# SCH_nb_v2_2022-07-07.net
KiCad netlist of a schematic drawn in EasyEDA
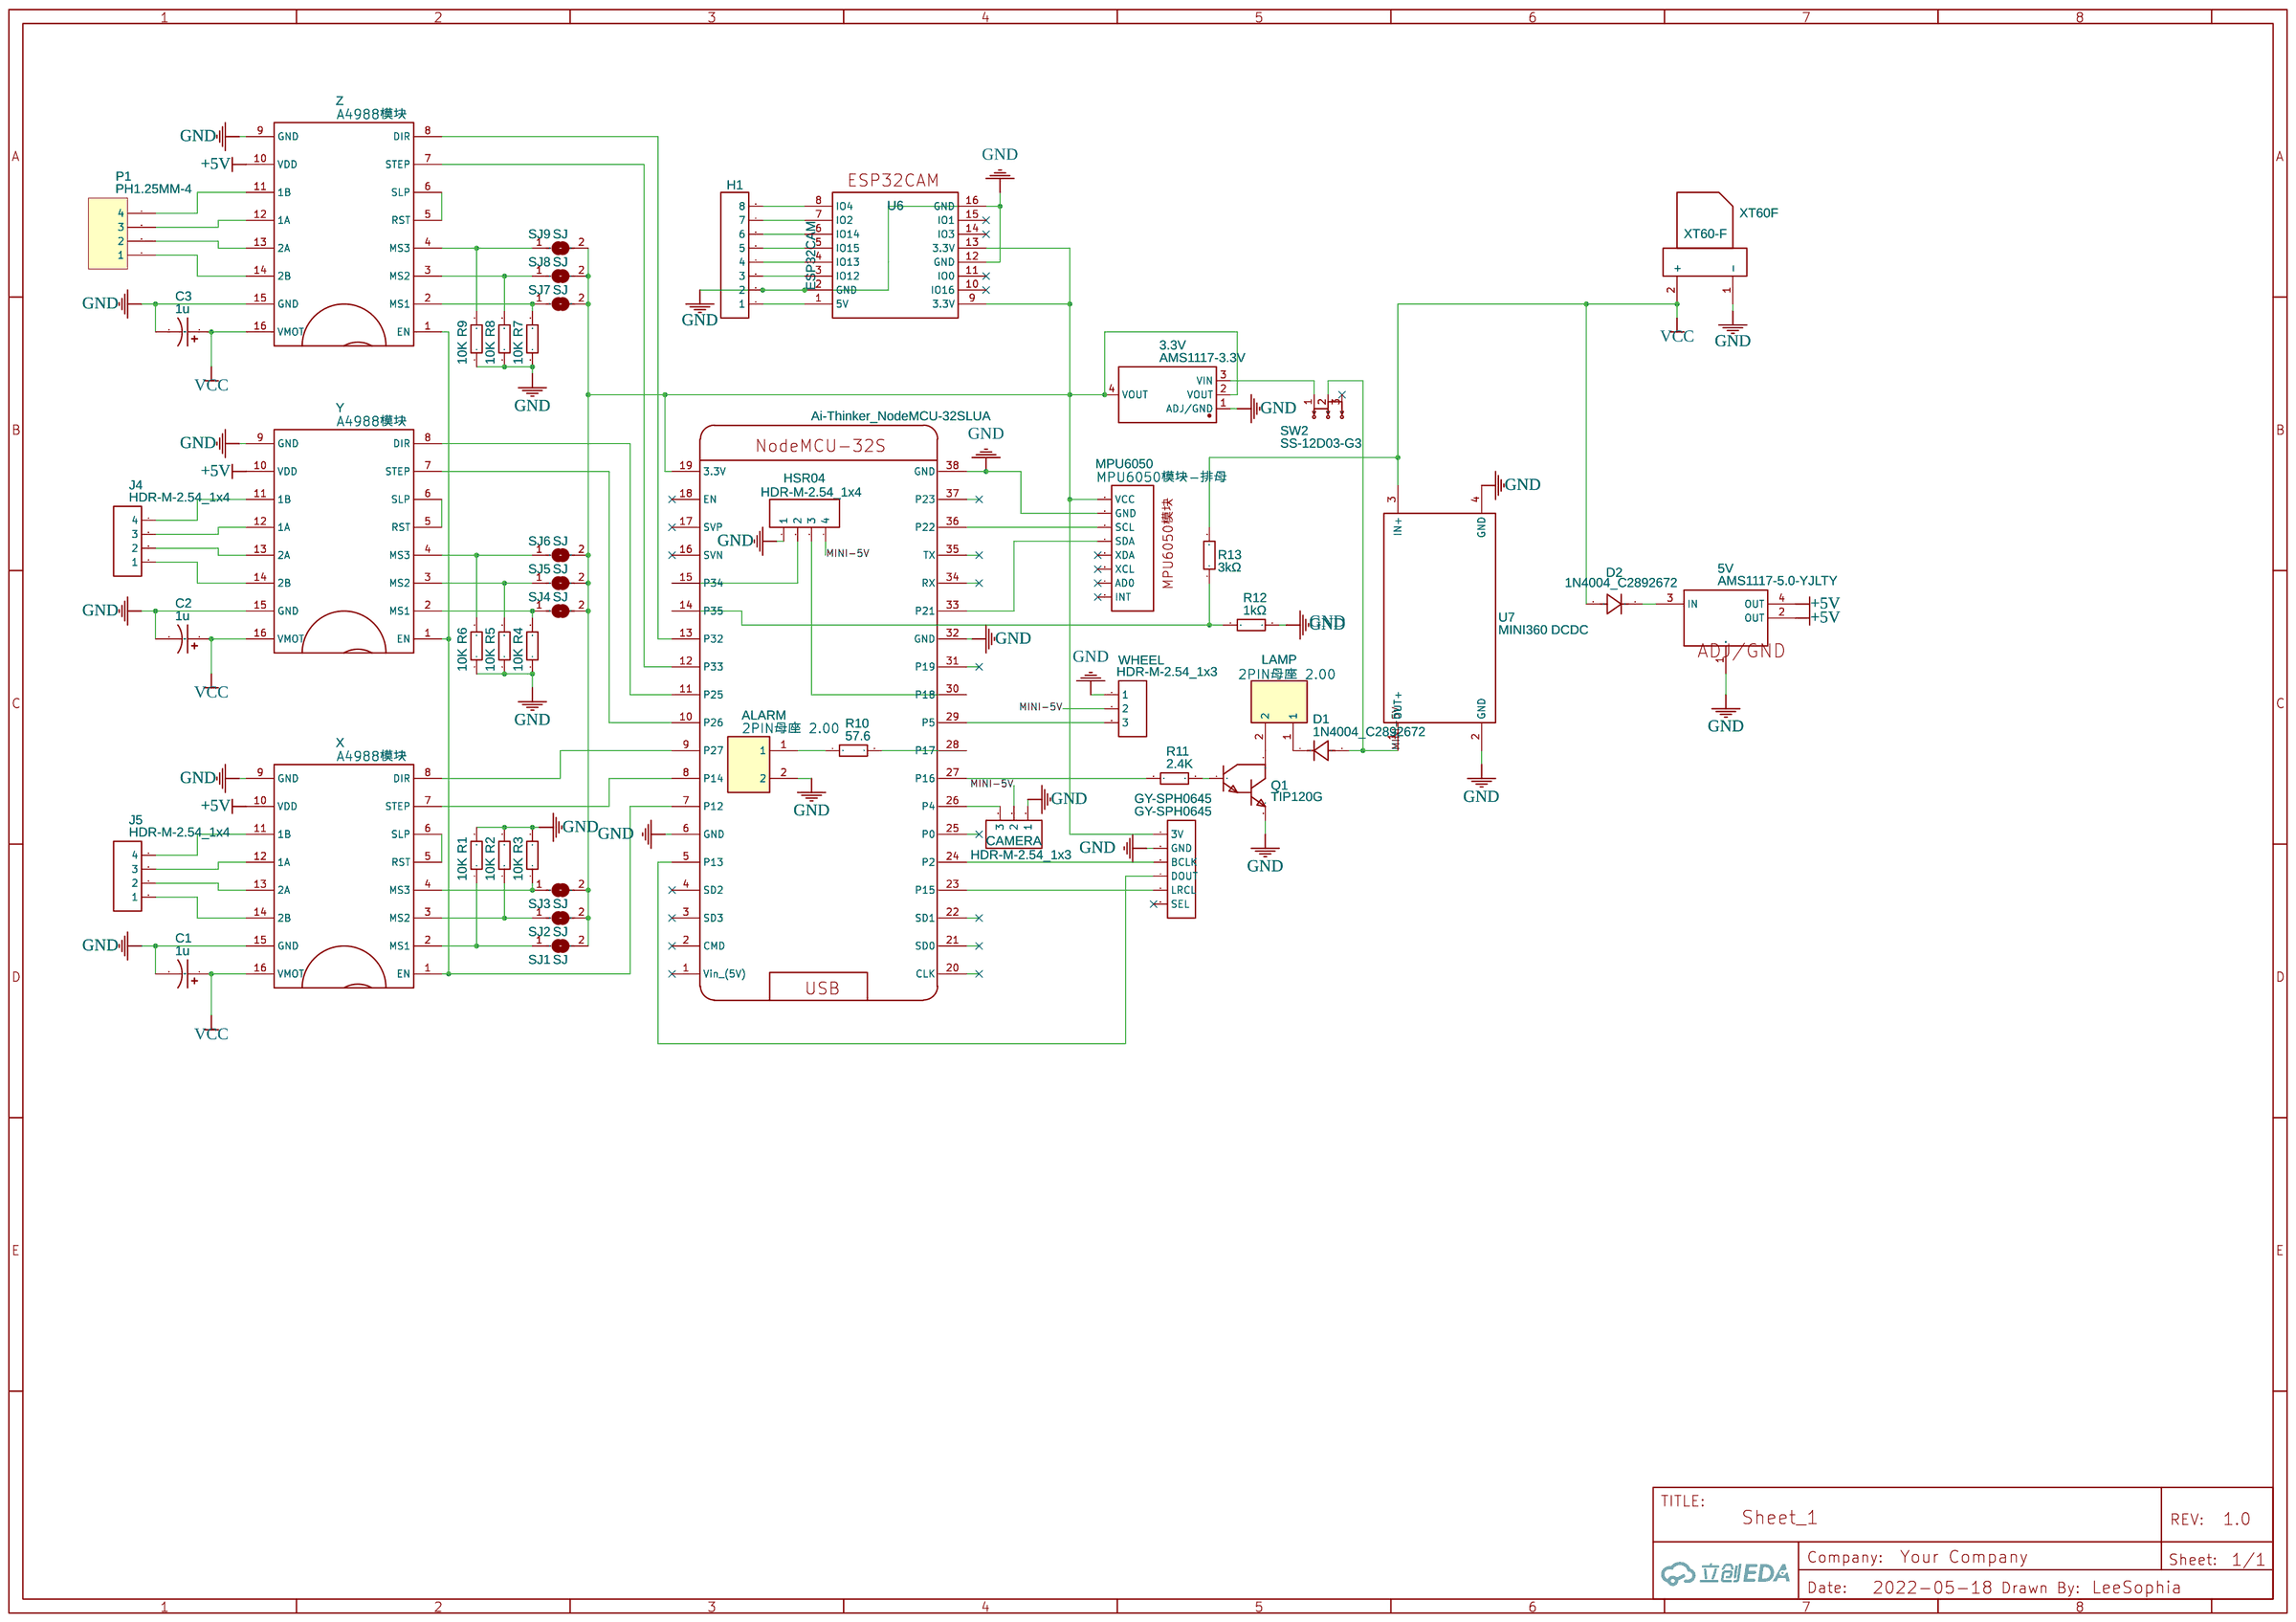
[diagram p0: schematic sheet]

(export (version "E")
  (design (tool "Eeschema 10.0.6"))
  (components
    (comp (ref "3.3V")
      (value "AMS1117-3.3V")
      (fields (field (name "BOM_Supplier Part") "C2688239"))
      (libsource (lib "") (part "AMS1117-3.3V"))
    )
    (comp (ref "5V")
      (value "AMS1117-5.0-YJLTY")
      (fields (field (name "BOM_Supplier Part") "C9900020131"))
      (libsource (lib "") (part "AMS1117-5.0-YJLTY"))
    )
    (comp (ref "ALARM")
      (value "2PIN母座 2.00")
      (fields (field (name "BOM_Manufacturer Part") "PH-2A") (field (name "BOM_Supplier Part") "C2319"))
      (libsource (lib "") (part "2PIN母座 2.00"))
    )
    (comp (ref "C1") (value "1u") (libsource (lib "") (part "CE_TH_D6.3×F2.5_US_1")))
    (comp (ref "C2") (value "1u") (libsource (lib "") (part "CE_TH_D6.3×F2.5_US")))
    (comp (ref "C3") (value "1u") (libsource (lib "") (part "CE_TH_D6.3×F2.5_US")))
    (comp (ref "CAMERA")
      (value "HDR-M-2.54_1x3")
      (fields (field (name "BOM_Supplier Part") "C180248"))
      (libsource (lib "") (part "HDR-M-2.54_1x3_1"))
    )
    (comp (ref "D1")
      (value "1N4004_C2892672")
      (fields (field (name "BOM_Manufacturer Part") "1N4004") (field (name "BOM_Supplier Part") "C2892672"))
      (libsource (lib "") (part "1N4004_C2892672_1"))
    )
    (comp (ref "D2")
      (value "1N4004_C2892672")
      (fields (field (name "BOM_Manufacturer Part") "1N4004") (field (name "BOM_Supplier Part") "C2892672"))
      (libsource (lib "") (part "1N4004_C2892672"))
    )
    (comp (ref "GY-SPH0645")
      (value "GY-SPH0645")
      (fields (field (name "BOM_Supplier Part") "C40877"))
      (libsource (lib "") (part "HDR-F-2.54_1x6"))
    )
    (comp (ref "H1")
      (value "H1")
      (fields (field (name "BOM_Supplier Part") "C225505"))
      (libsource (lib "") (part "HDR-F-2.54_1x8"))
    )
    (comp (ref "HSR04")
      (value "HDR-M-2.54_1x4")
      (fields (field (name "BOM_Supplier Part") "C124378"))
      (libsource (lib "") (part "HDR-M-2.54_1x4_1"))
    )
    (comp (ref "J4")
      (value "HDR-M-2.54_1x4")
      (fields (field (name "BOM_Supplier Part") "C124378"))
      (libsource (lib "") (part "HDR-M-2.54_1x4"))
    )
    (comp (ref "J5")
      (value "HDR-M-2.54_1x4")
      (fields (field (name "BOM_Supplier Part") "C124378"))
      (libsource (lib "") (part "HDR-M-2.54_1x4"))
    )
    (comp (ref "LAMP")
      (value "2PIN母座 2.00")
      (fields (field (name "BOM_Manufacturer Part") "PH-2A") (field (name "BOM_Supplier Part") "C2319"))
      (libsource (lib "") (part "2PIN母座 2.00_1"))
    )
    (comp (ref "MPU6050") (value "MPU6050模块-排母") (libsource (lib "") (part "MPU6050模块-排母")))
    (comp (ref "P1") (value "PH1.25MM-4") (libsource (lib "") (part "PH1.25MM-4")))
    (comp (ref "Q1")
      (value "TIP120G")
      (fields (field (name "BOM_Supplier Part") "C223613"))
      (libsource (lib "") (part "TIP120G"))
    )
    (comp (ref "R1")
      (value "10K")
      (fields
        (field (name "BOM_Manufacturer Part") "RMCF0603JT10K0")
        (field (name "BOM_Supplier Part") "C238881")
      )
      (libsource (lib "") (part "RMCF0603JT10K0"))
    )
    (comp (ref "R2")
      (value "10K")
      (fields
        (field (name "BOM_Manufacturer Part") "RMCF0603JT10K0")
        (field (name "BOM_Supplier Part") "C238881")
      )
      (libsource (lib "") (part "RMCF0603JT10K0"))
    )
    (comp (ref "R3")
      (value "10K")
      (fields
        (field (name "BOM_Manufacturer Part") "RMCF0603JT10K0")
        (field (name "BOM_Supplier Part") "C238881")
      )
      (libsource (lib "") (part "RMCF0603JT10K0"))
    )
    (comp (ref "R4")
      (value "10K")
      (fields
        (field (name "BOM_Manufacturer Part") "RMCF0603JT10K0")
        (field (name "BOM_Supplier Part") "C238881")
      )
      (libsource (lib "") (part "RMCF0603JT10K0"))
    )
    (comp (ref "R5")
      (value "10K")
      (fields
        (field (name "BOM_Manufacturer Part") "RMCF0603JT10K0")
        (field (name "BOM_Supplier Part") "C238881")
      )
      (libsource (lib "") (part "RMCF0603JT10K0"))
    )
    (comp (ref "R6")
      (value "10K")
      (fields
        (field (name "BOM_Manufacturer Part") "RMCF0603JT10K0")
        (field (name "BOM_Supplier Part") "C238881")
      )
      (libsource (lib "") (part "RMCF0603JT10K0"))
    )
    (comp (ref "R7")
      (value "10K")
      (fields
        (field (name "BOM_Manufacturer Part") "RMCF0603JT10K0")
        (field (name "BOM_Supplier Part") "C238881")
      )
      (libsource (lib "") (part "RMCF0603JT10K0"))
    )
    (comp (ref "R8")
      (value "10K")
      (fields
        (field (name "BOM_Manufacturer Part") "RMCF0603JT10K0")
        (field (name "BOM_Supplier Part") "C238881")
      )
      (libsource (lib "") (part "RMCF0603JT10K0"))
    )
    (comp (ref "R9")
      (value "10K")
      (fields
        (field (name "BOM_Manufacturer Part") "RMCF0603JT10K0")
        (field (name "BOM_Supplier Part") "C238881")
      )
      (libsource (lib "") (part "RMCF0603JT10K0"))
    )
    (comp (ref "R10")
      (value "57.6")
      (fields
        (field (name "BOM_Manufacturer Part") "RC0603FR-0757R6L")
        (field (name "BOM_Supplier Part") "C245984")
      )
      (libsource (lib "") (part "RC0603FR-0757R6L"))
    )
    (comp (ref "R11")
      (value "2.4K")
      (fields
        (field (name "BOM_Manufacturer Part") "AC0603FR-072K4L")
        (field (name "BOM_Supplier Part") "C144674")
      )
      (libsource (lib "") (part "AC0603FR-072K4L"))
    )
    (comp (ref "R12")
      (value "1kΩ")
      (fields
        (field (name "BOM_Manufacturer Part") "0603WAF1101T5E")
        (field (name "BOM_Supplier Part") "C22764")
      )
      (libsource (lib "") (part "0603WAF1101T5E"))
    )
    (comp (ref "R13")
      (value "3kΩ")
      (fields
        (field (name "BOM_Manufacturer Part") "RM06FTN3001")
        (field (name "BOM_Supplier Part") "C147818")
      )
      (libsource (lib "") (part "RM06FTN3001"))
    )
    (comp (ref "SJ1") (value "SJ") (libsource (lib "") (part "SJ")))
    (comp (ref "SJ2") (value "SJ") (libsource (lib "") (part "SJ")))
    (comp (ref "SJ3") (value "SJ") (libsource (lib "") (part "SJ")))
    (comp (ref "SJ4") (value "SJ") (libsource (lib "") (part "SJ")))
    (comp (ref "SJ5") (value "SJ") (libsource (lib "") (part "SJ")))
    (comp (ref "SJ6") (value "SJ") (libsource (lib "") (part "SJ")))
    (comp (ref "SJ7") (value "SJ") (libsource (lib "") (part "SJ")))
    (comp (ref "SJ8") (value "SJ") (libsource (lib "") (part "SJ")))
    (comp (ref "SJ9") (value "SJ") (libsource (lib "") (part "SJ")))
    (comp (ref "SW2")
      (value "SS-12D03-G3")
      (fields (field (name "BOM_Supplier Part") "C698224"))
      (libsource (lib "") (part "SS-12D03-G3"))
    )
    (comp (ref "U2")
      (value "Ai-Thinker_NodeMCU-32SLUA")
      (fields
        (field (name "BOM_Manufacturer Part") "NodeMCU-32SLua")
        (field (name "BOM_Supplier Part") "C111436")
      )
      (libsource (lib "") (part "Ai-Thinker_NodeMCU-32SLUA"))
    )
    (comp (ref "U6") (value "ESP32CAM") (libsource (lib "") (part "ESP32CAM")))
    (comp (ref "U7") (value "MINI360 DCDC") (libsource (lib "") (part "MINI360 DCDC")))
    (comp (ref "WHEEL")
      (value "HDR-M-2.54_1x3")
      (fields (field (name "BOM_Supplier Part") "C180248"))
      (libsource (lib "") (part "HDR-M-2.54_1x3"))
    )
    (comp (ref "X") (value "A4988模块") (libsource (lib "") (part "A4988模块_1")))
    (comp (ref "XT60F") (value "XT60-F") (libsource (lib "") (part "XT60-F")))
    (comp (ref "Y") (value "A4988模块") (libsource (lib "") (part "A4988模块_2")))
    (comp (ref "Z") (value "A4988模块") (libsource (lib "") (part "A4988模块")))
  )
  (nets
    (net (code "1") (name "+5V") (class "Default")
      (node (ref "5V") (pin "2") (pinfunction "OUT_2") (pintype "passive"))
      (node (ref "5V") (pin "4") (pinfunction "OUT_4") (pintype "passive"))
      (node (ref "X") (pin "10") (pinfunction "VDD_10") (pintype "passive"))
      (node (ref "Y") (pin "10") (pinfunction "VDD_10") (pintype "passive"))
      (node (ref "Z") (pin "10") (pinfunction "VDD_10") (pintype "passive"))
    )
    (net (code "2") (name "/MINI-5V") (class "Default")
      (node (ref "CAMERA") (pin "2") (pinfunction "2_2") (pintype "input"))
      (node (ref "D1") (pin "2") (pinfunction "A_2") (pintype "unspecified"))
      (node (ref "HSR04") (pin "4") (pinfunction "4_4") (pintype "unspecified"))
      (node (ref "SW2") (pin "2") (pinfunction "2_2") (pintype "unspecified"))
      (node (ref "U7") (pin "1") (pinfunction "OUT+_1") (pintype "unspecified"))
      (node (ref "WHEEL") (pin "2") (pinfunction "2_2") (pintype "input"))
    )
    (net (code "3") (name "GND") (class "Default")
      (node (ref "3.3V") (pin "1") (pinfunction "ADJ/GND_1") (pintype "unspecified"))
      (node (ref "5V") (pin "1") (pinfunction "ADJ/GND_1") (pintype "passive"))
      (node (ref "ALARM") (pin "2") (pinfunction "2_2") (pintype "input"))
      (node (ref "C1") (pin "2") (pinfunction "2_2") (pintype "unspecified"))
      (node (ref "C2") (pin "2") (pinfunction "2_2") (pintype "unspecified"))
      (node (ref "C3") (pin "2") (pinfunction "2_2") (pintype "unspecified"))
      (node (ref "CAMERA") (pin "1") (pinfunction "1_1") (pintype "input"))
      (node (ref "GY-SPH0645") (pin "2") (pinfunction "GND_2") (pintype "input"))
      (node (ref "H1") (pin "2") (pinfunction "2_2") (pintype "unspecified"))
      (node (ref "HSR04") (pin "1") (pinfunction "1_1") (pintype "unspecified"))
      (node (ref "MPU6050") (pin "2") (pinfunction "GND_2") (pintype "input"))
      (node (ref "Q1") (pin "3") (pinfunction "E_3") (pintype "unspecified"))
      (node (ref "R1") (pin "2") (pinfunction "2_2") (pintype "unspecified"))
      (node (ref "R12") (pin "2") (pinfunction "2_2") (pintype "input"))
      (node (ref "R2") (pin "2") (pinfunction "2_2") (pintype "unspecified"))
      (node (ref "R3") (pin "2") (pinfunction "2_2") (pintype "unspecified"))
      (node (ref "R4") (pin "1") (pinfunction "1_1") (pintype "unspecified"))
      (node (ref "R5") (pin "1") (pinfunction "1_1") (pintype "unspecified"))
      (node (ref "R6") (pin "1") (pinfunction "1_1") (pintype "unspecified"))
      (node (ref "R7") (pin "1") (pinfunction "1_1") (pintype "unspecified"))
      (node (ref "R8") (pin "1") (pinfunction "1_1") (pintype "unspecified"))
      (node (ref "R9") (pin "1") (pinfunction "1_1") (pintype "unspecified"))
      (node (ref "U2") (pin "32") (pinfunction "GND_32") (pintype "unspecified"))
      (node (ref "U2") (pin "38") (pinfunction "GND_38") (pintype "unspecified"))
      (node (ref "U2") (pin "6") (pinfunction "GND_6") (pintype "unspecified"))
      (node (ref "U6") (pin "12") (pinfunction "GND_12") (pintype "unspecified"))
      (node (ref "U6") (pin "16") (pinfunction "GND_16") (pintype "unspecified"))
      (node (ref "U6") (pin "2") (pinfunction "GND_2") (pintype "unspecified"))
      (node (ref "U7") (pin "2") (pinfunction "GND_2") (pintype "unspecified"))
      (node (ref "U7") (pin "4") (pinfunction "GND_4") (pintype "unspecified"))
      (node (ref "WHEEL") (pin "1") (pinfunction "1_1") (pintype "input"))
      (node (ref "X") (pin "15") (pinfunction "GND_15") (pintype "passive"))
      (node (ref "X") (pin "9") (pinfunction "GND_9") (pintype "passive"))
      (node (ref "XT60F") (pin "1") (pinfunction "-_1") (pintype "unspecified"))
      (node (ref "Y") (pin "15") (pinfunction "GND_15") (pintype "passive"))
      (node (ref "Y") (pin "9") (pinfunction "GND_9") (pintype "passive"))
      (node (ref "Z") (pin "15") (pinfunction "GND_15") (pintype "passive"))
      (node (ref "Z") (pin "9") (pinfunction "GND_9") (pintype "passive"))
    )
    (net (code "4") (name "Net-(3.3V-VIN)") (class "Default")
      (node (ref "3.3V") (pin "3") (pinfunction "VIN_3") (pintype "unspecified"))
      (node (ref "SW2") (pin "1") (pinfunction "1_1") (pintype "unspecified"))
    )
    (net (code "5") (name "Net-(5V-IN)") (class "Default")
      (node (ref "5V") (pin "3") (pinfunction "IN_3") (pintype "passive"))
      (node (ref "D2") (pin "1") (pinfunction "K_1") (pintype "unspecified"))
    )
    (net (code "6") (name "Net-(ALARM-Pad1)") (class "Default")
      (node (ref "ALARM") (pin "1") (pinfunction "1_1") (pintype "input"))
      (node (ref "R10") (pin "1") (pinfunction "1_1") (pintype "unspecified"))
    )
    (net (code "7") (name "Net-(D1-K)") (class "Default")
      (node (ref "D1") (pin "1") (pinfunction "K_1") (pintype "unspecified"))
      (node (ref "LAMP") (pin "1") (pinfunction "1_1") (pintype "input"))
    )
    (net (code "8") (name "Net-(GY-SPH0645-3V)") (class "Default")
      (node (ref "3.3V") (pin "2") (pinfunction "VOUT_2") (pintype "unspecified"))
      (node (ref "3.3V") (pin "4") (pinfunction "VOUT_4") (pintype "unspecified"))
      (node (ref "GY-SPH0645") (pin "1") (pinfunction "3V_1") (pintype "input"))
      (node (ref "MPU6050") (pin "1") (pinfunction "VCC_1") (pintype "input"))
      (node (ref "SJ1") (pin "2") (pinfunction "2_2") (pintype "bidirectional"))
      (node (ref "SJ2") (pin "2") (pinfunction "2_2") (pintype "bidirectional"))
      (node (ref "SJ3") (pin "2") (pinfunction "2_2") (pintype "bidirectional"))
      (node (ref "SJ4") (pin "2") (pinfunction "2_2") (pintype "bidirectional"))
      (node (ref "SJ5") (pin "2") (pinfunction "2_2") (pintype "bidirectional"))
      (node (ref "SJ6") (pin "2") (pinfunction "2_2") (pintype "bidirectional"))
      (node (ref "SJ7") (pin "2") (pinfunction "2_2") (pintype "bidirectional"))
      (node (ref "SJ8") (pin "2") (pinfunction "2_2") (pintype "bidirectional"))
      (node (ref "SJ9") (pin "2") (pinfunction "2_2") (pintype "bidirectional"))
      (node (ref "U2") (pin "19") (pinfunction "3.3V_19") (pintype "unspecified"))
      (node (ref "U6") (pin "13") (pinfunction "3.3V_13") (pintype "unspecified"))
      (node (ref "U6") (pin "9") (pinfunction "3.3V_9") (pintype "unspecified"))
    )
    (net (code "9") (name "Net-(GY-SPH0645-BCLK)") (class "Default")
      (node (ref "GY-SPH0645") (pin "3") (pinfunction "BCLK_3") (pintype "input"))
      (node (ref "U2") (pin "24") (pinfunction "P2_24") (pintype "unspecified"))
    )
    (net (code "10") (name "Net-(GY-SPH0645-DOUT)") (class "Default")
      (node (ref "GY-SPH0645") (pin "4") (pinfunction "DOUT_4") (pintype "input"))
      (node (ref "U2") (pin "5") (pinfunction "P13_5") (pintype "unspecified"))
    )
    (net (code "11") (name "Net-(GY-SPH0645-LRCL)") (class "Default")
      (node (ref "GY-SPH0645") (pin "5") (pinfunction "LRCL_5") (pintype "input"))
      (node (ref "U2") (pin "23") (pinfunction "P15_23") (pintype "unspecified"))
    )
    (net (code "12") (name "Net-(MPU6050-SCL)") (class "Default")
      (node (ref "MPU6050") (pin "3") (pinfunction "SCL_3") (pintype "input"))
      (node (ref "U2") (pin "36") (pinfunction "P22_36") (pintype "unspecified"))
    )
    (net (code "13") (name "Net-(MPU6050-SDA)") (class "Default")
      (node (ref "MPU6050") (pin "4") (pinfunction "SDA_4") (pintype "input"))
      (node (ref "U2") (pin "33") (pinfunction "P21_33") (pintype "unspecified"))
    )
    (net (code "14") (name "Net-(Q1-B)") (class "Default")
      (node (ref "Q1") (pin "1") (pinfunction "B_1") (pintype "unspecified"))
      (node (ref "R11") (pin "2") (pinfunction "2_2") (pintype "unspecified"))
    )
    (net (code "15") (name "Net-(Q1-C)") (class "Default")
      (node (ref "LAMP") (pin "2") (pinfunction "2_2") (pintype "input"))
      (node (ref "Q1") (pin "2") (pinfunction "C_2") (pintype "unspecified"))
    )
    (net (code "16") (name "Net-(U2-P4)") (class "Default")
      (node (ref "CAMERA") (pin "3") (pinfunction "3_3") (pintype "input"))
      (node (ref "U2") (pin "26") (pinfunction "P4_26") (pintype "unspecified"))
    )
    (net (code "17") (name "Net-(U2-P5)") (class "Default")
      (node (ref "U2") (pin "29") (pinfunction "P5_29") (pintype "unspecified"))
      (node (ref "WHEEL") (pin "3") (pinfunction "3_3") (pintype "input"))
    )
    (net (code "18") (name "Net-(U2-P12)") (class "Default")
      (node (ref "U2") (pin "7") (pinfunction "P12_7") (pintype "unspecified"))
      (node (ref "X") (pin "1") (pinfunction "EN_1") (pintype "input"))
      (node (ref "Y") (pin "1") (pinfunction "EN_1") (pintype "input"))
      (node (ref "Z") (pin "1") (pinfunction "EN_1") (pintype "input"))
    )
    (net (code "19") (name "Net-(U2-P14)") (class "Default")
      (node (ref "U2") (pin "8") (pinfunction "P14_8") (pintype "unspecified"))
      (node (ref "X") (pin "7") (pinfunction "STEP_7") (pintype "input"))
    )
    (net (code "20") (name "Net-(U2-P16)") (class "Default")
      (node (ref "R11") (pin "1") (pinfunction "1_1") (pintype "unspecified"))
      (node (ref "U2") (pin "27") (pinfunction "P16_27") (pintype "unspecified"))
    )
    (net (code "21") (name "Net-(U2-P17)") (class "Default")
      (node (ref "R10") (pin "2") (pinfunction "2_2") (pintype "unspecified"))
      (node (ref "U2") (pin "28") (pinfunction "P17_28") (pintype "unspecified"))
    )
    (net (code "22") (name "Net-(U2-P18)") (class "Default")
      (node (ref "HSR04") (pin "3") (pinfunction "3_3") (pintype "unspecified"))
      (node (ref "U2") (pin "30") (pinfunction "P18_30") (pintype "unspecified"))
    )
    (net (code "23") (name "Net-(U2-P25)") (class "Default")
      (node (ref "U2") (pin "11") (pinfunction "P25_11") (pintype "unspecified"))
      (node (ref "Y") (pin "8") (pinfunction "DIR_8") (pintype "input"))
    )
    (net (code "24") (name "Net-(U2-P26)") (class "Default")
      (node (ref "U2") (pin "10") (pinfunction "P26_10") (pintype "unspecified"))
      (node (ref "Y") (pin "7") (pinfunction "STEP_7") (pintype "input"))
    )
    (net (code "25") (name "Net-(U2-P27)") (class "Default")
      (node (ref "U2") (pin "9") (pinfunction "P27_9") (pintype "unspecified"))
      (node (ref "X") (pin "8") (pinfunction "DIR_8") (pintype "input"))
    )
    (net (code "26") (name "Net-(U2-P32)") (class "Default")
      (node (ref "U2") (pin "13") (pinfunction "P32_13") (pintype "unspecified"))
      (node (ref "Z") (pin "8") (pinfunction "DIR_8") (pintype "input"))
    )
    (net (code "27") (name "Net-(U2-P33)") (class "Default")
      (node (ref "U2") (pin "12") (pinfunction "P33_12") (pintype "unspecified"))
      (node (ref "Z") (pin "7") (pinfunction "STEP_7") (pintype "input"))
    )
    (net (code "28") (name "Net-(U2-P34)") (class "Default")
      (node (ref "HSR04") (pin "2") (pinfunction "2_2") (pintype "unspecified"))
      (node (ref "U2") (pin "15") (pinfunction "P34_15") (pintype "unspecified"))
    )
    (net (code "29") (name "Net-(U2-P35)") (class "Default")
      (node (ref "R12") (pin "1") (pinfunction "1_1") (pintype "input"))
      (node (ref "R13") (pin "1") (pinfunction "1_1") (pintype "unspecified"))
      (node (ref "U2") (pin "14") (pinfunction "P35_14") (pintype "unspecified"))
    )
    (net (code "30") (name "Net-(U6-5V)") (class "Default")
      (node (ref "H1") (pin "1") (pinfunction "1_1") (pintype "unspecified"))
      (node (ref "U6") (pin "1") (pinfunction "5V_1") (pintype "unspecified"))
    )
    (net (code "31") (name "Net-(U6-IO2)") (class "Default")
      (node (ref "H1") (pin "7") (pinfunction "7_7") (pintype "unspecified"))
      (node (ref "U6") (pin "7") (pinfunction "IO2_7") (pintype "unspecified"))
    )
    (net (code "32") (name "Net-(U6-IO4)") (class "Default")
      (node (ref "H1") (pin "8") (pinfunction "8_8") (pintype "unspecified"))
      (node (ref "U6") (pin "8") (pinfunction "IO4_8") (pintype "unspecified"))
    )
    (net (code "33") (name "Net-(U6-IO12)") (class "Default")
      (node (ref "H1") (pin "3") (pinfunction "3_3") (pintype "unspecified"))
      (node (ref "U6") (pin "3") (pinfunction "IO12_3") (pintype "unspecified"))
    )
    (net (code "34") (name "Net-(U6-IO13)") (class "Default")
      (node (ref "H1") (pin "4") (pinfunction "4_4") (pintype "unspecified"))
      (node (ref "U6") (pin "4") (pinfunction "IO13_4") (pintype "unspecified"))
    )
    (net (code "35") (name "Net-(U6-IO14)") (class "Default")
      (node (ref "H1") (pin "6") (pinfunction "6_6") (pintype "unspecified"))
      (node (ref "U6") (pin "6") (pinfunction "IO14_6") (pintype "unspecified"))
    )
    (net (code "36") (name "Net-(U6-IO15)") (class "Default")
      (node (ref "H1") (pin "5") (pinfunction "5_5") (pintype "unspecified"))
      (node (ref "U6") (pin "5") (pinfunction "IO15_5") (pintype "unspecified"))
    )
    (net (code "37") (name "Net-(X-1A)") (class "Default")
      (node (ref "J5") (pin "3") (pinfunction "3_3") (pintype "unspecified"))
      (node (ref "X") (pin "12") (pinfunction "1A_12") (pintype "output"))
    )
    (net (code "38") (name "Net-(X-1B)") (class "Default")
      (node (ref "J5") (pin "4") (pinfunction "4_4") (pintype "unspecified"))
      (node (ref "X") (pin "11") (pinfunction "1B_11") (pintype "output"))
    )
    (net (code "39") (name "Net-(X-2A)") (class "Default")
      (node (ref "J5") (pin "2") (pinfunction "2_2") (pintype "unspecified"))
      (node (ref "X") (pin "13") (pinfunction "2A_13") (pintype "output"))
    )
    (net (code "40") (name "Net-(X-2B)") (class "Default")
      (node (ref "J5") (pin "1") (pinfunction "1_1") (pintype "unspecified"))
      (node (ref "X") (pin "14") (pinfunction "2B_14") (pintype "output"))
    )
    (net (code "41") (name "Net-(X-MS1)") (class "Default")
      (node (ref "R1") (pin "1") (pinfunction "1_1") (pintype "unspecified"))
      (node (ref "SJ1") (pin "1") (pinfunction "1_1") (pintype "bidirectional"))
      (node (ref "X") (pin "2") (pinfunction "MS1_2") (pintype "input"))
    )
    (net (code "42") (name "Net-(X-MS2)") (class "Default")
      (node (ref "R2") (pin "1") (pinfunction "1_1") (pintype "unspecified"))
      (node (ref "SJ2") (pin "1") (pinfunction "1_1") (pintype "bidirectional"))
      (node (ref "X") (pin "3") (pinfunction "MS2_3") (pintype "input"))
    )
    (net (code "43") (name "Net-(X-MS3)") (class "Default")
      (node (ref "R3") (pin "1") (pinfunction "1_1") (pintype "unspecified"))
      (node (ref "SJ3") (pin "1") (pinfunction "1_1") (pintype "bidirectional"))
      (node (ref "X") (pin "4") (pinfunction "MS3_4") (pintype "input"))
    )
    (net (code "44") (name "Net-(X-RST)") (class "Default")
      (node (ref "X") (pin "5") (pinfunction "RST_5") (pintype "input"))
      (node (ref "X") (pin "6") (pinfunction "SLP_6") (pintype "input"))
    )
    (net (code "45") (name "Net-(Y-1A)") (class "Default")
      (node (ref "J4") (pin "3") (pinfunction "3_3") (pintype "unspecified"))
      (node (ref "Y") (pin "12") (pinfunction "1A_12") (pintype "output"))
    )
    (net (code "46") (name "Net-(Y-1B)") (class "Default")
      (node (ref "J4") (pin "4") (pinfunction "4_4") (pintype "unspecified"))
      (node (ref "Y") (pin "11") (pinfunction "1B_11") (pintype "output"))
    )
    (net (code "47") (name "Net-(Y-2A)") (class "Default")
      (node (ref "J4") (pin "2") (pinfunction "2_2") (pintype "unspecified"))
      (node (ref "Y") (pin "13") (pinfunction "2A_13") (pintype "output"))
    )
    (net (code "48") (name "Net-(Y-2B)") (class "Default")
      (node (ref "J4") (pin "1") (pinfunction "1_1") (pintype "unspecified"))
      (node (ref "Y") (pin "14") (pinfunction "2B_14") (pintype "output"))
    )
    (net (code "49") (name "Net-(Y-MS1)") (class "Default")
      (node (ref "R4") (pin "2") (pinfunction "2_2") (pintype "unspecified"))
      (node (ref "SJ4") (pin "1") (pinfunction "1_1") (pintype "bidirectional"))
      (node (ref "Y") (pin "2") (pinfunction "MS1_2") (pintype "input"))
    )
    (net (code "50") (name "Net-(Y-MS2)") (class "Default")
      (node (ref "R5") (pin "2") (pinfunction "2_2") (pintype "unspecified"))
      (node (ref "SJ5") (pin "1") (pinfunction "1_1") (pintype "bidirectional"))
      (node (ref "Y") (pin "3") (pinfunction "MS2_3") (pintype "input"))
    )
    (net (code "51") (name "Net-(Y-MS3)") (class "Default")
      (node (ref "R6") (pin "2") (pinfunction "2_2") (pintype "unspecified"))
      (node (ref "SJ6") (pin "1") (pinfunction "1_1") (pintype "bidirectional"))
      (node (ref "Y") (pin "4") (pinfunction "MS3_4") (pintype "input"))
    )
    (net (code "52") (name "Net-(Y-RST)") (class "Default")
      (node (ref "Y") (pin "5") (pinfunction "RST_5") (pintype "input"))
      (node (ref "Y") (pin "6") (pinfunction "SLP_6") (pintype "input"))
    )
    (net (code "53") (name "Net-(Z-1A)") (class "Default")
      (node (ref "P1") (pin "3") (pinfunction "3_3") (pintype "unspecified"))
      (node (ref "Z") (pin "12") (pinfunction "1A_12") (pintype "output"))
    )
    (net (code "54") (name "Net-(Z-1B)") (class "Default")
      (node (ref "P1") (pin "4") (pinfunction "4_4") (pintype "unspecified"))
      (node (ref "Z") (pin "11") (pinfunction "1B_11") (pintype "output"))
    )
    (net (code "55") (name "Net-(Z-2A)") (class "Default")
      (node (ref "P1") (pin "2") (pinfunction "2_2") (pintype "unspecified"))
      (node (ref "Z") (pin "13") (pinfunction "2A_13") (pintype "output"))
    )
    (net (code "56") (name "Net-(Z-2B)") (class "Default")
      (node (ref "P1") (pin "1") (pinfunction "1_1") (pintype "unspecified"))
      (node (ref "Z") (pin "14") (pinfunction "2B_14") (pintype "output"))
    )
    (net (code "57") (name "Net-(Z-MS1)") (class "Default")
      (node (ref "R7") (pin "2") (pinfunction "2_2") (pintype "unspecified"))
      (node (ref "SJ7") (pin "1") (pinfunction "1_1") (pintype "bidirectional"))
      (node (ref "Z") (pin "2") (pinfunction "MS1_2") (pintype "input"))
    )
    (net (code "58") (name "Net-(Z-MS2)") (class "Default")
      (node (ref "R8") (pin "2") (pinfunction "2_2") (pintype "unspecified"))
      (node (ref "SJ8") (pin "1") (pinfunction "1_1") (pintype "bidirectional"))
      (node (ref "Z") (pin "3") (pinfunction "MS2_3") (pintype "input"))
    )
    (net (code "59") (name "Net-(Z-MS3)") (class "Default")
      (node (ref "R9") (pin "2") (pinfunction "2_2") (pintype "unspecified"))
      (node (ref "SJ9") (pin "1") (pinfunction "1_1") (pintype "bidirectional"))
      (node (ref "Z") (pin "4") (pinfunction "MS3_4") (pintype "input"))
    )
    (net (code "60") (name "Net-(Z-RST)") (class "Default")
      (node (ref "Z") (pin "5") (pinfunction "RST_5") (pintype "input"))
      (node (ref "Z") (pin "6") (pinfunction "SLP_6") (pintype "input"))
    )
    (net (code "61") (name "VCC") (class "Default")
      (node (ref "C1") (pin "1") (pinfunction "1_1") (pintype "unspecified"))
      (node (ref "C2") (pin "1") (pinfunction "1_1") (pintype "unspecified"))
      (node (ref "C3") (pin "1") (pinfunction "1_1") (pintype "unspecified"))
      (node (ref "D2") (pin "2") (pinfunction "A_2") (pintype "unspecified"))
      (node (ref "R13") (pin "2") (pinfunction "2_2") (pintype "unspecified"))
      (node (ref "U7") (pin "3") (pinfunction "IN+_3") (pintype "unspecified"))
      (node (ref "X") (pin "16") (pinfunction "VMOT_16") (pintype "passive"))
      (node (ref "XT60F") (pin "2") (pinfunction "+_2") (pintype "unspecified"))
      (node (ref "Y") (pin "16") (pinfunction "VMOT_16") (pintype "passive"))
      (node (ref "Z") (pin "16") (pinfunction "VMOT_16") (pintype "passive"))
    )
    (net (code "62") (name "unconnected-(GY-SPH0645-SEL-Pad6)") (class "Default")
      (node (ref "GY-SPH0645") (pin "6") (pinfunction "SEL_6") (pintype "input+no_connect"))
    )
    (net (code "63") (name "unconnected-(MPU6050-AD0-Pad7)") (class "Default")
      (node (ref "MPU6050") (pin "7") (pinfunction "AD0_7") (pintype "input+no_connect"))
    )
    (net (code "64") (name "unconnected-(MPU6050-INT-Pad8)") (class "Default")
      (node (ref "MPU6050") (pin "8") (pinfunction "INT_8") (pintype "input+no_connect"))
    )
    (net (code "65") (name "unconnected-(MPU6050-XCL-Pad6)") (class "Default")
      (node (ref "MPU6050") (pin "6") (pinfunction "XCL_6") (pintype "input+no_connect"))
    )
    (net (code "66") (name "unconnected-(MPU6050-XDA-Pad5)") (class "Default")
      (node (ref "MPU6050") (pin "5") (pinfunction "XDA_5") (pintype "input+no_connect"))
    )
    (net (code "67") (name "unconnected-(SW2-Pad3)") (class "Default")
      (node (ref "SW2") (pin "3") (pinfunction "3_3") (pintype "unspecified+no_connect"))
    )
    (net (code "68") (name "unconnected-(U2-CLK-Pad20)") (class "Default")
      (node (ref "U2") (pin "20") (pinfunction "CLK_20") (pintype "unspecified+no_connect"))
    )
    (net (code "69") (name "unconnected-(U2-CMD-Pad2)") (class "Default")
      (node (ref "U2") (pin "2") (pinfunction "CMD_2") (pintype "unspecified+no_connect"))
    )
    (net (code "70") (name "unconnected-(U2-EN-Pad18)") (class "Default")
      (node (ref "U2") (pin "18") (pinfunction "EN_18") (pintype "unspecified+no_connect"))
    )
    (net (code "71") (name "unconnected-(U2-P0-Pad25)") (class "Default")
      (node (ref "U2") (pin "25") (pinfunction "P0_25") (pintype "unspecified+no_connect"))
    )
    (net (code "72") (name "unconnected-(U2-P19-Pad31)") (class "Default")
      (node (ref "U2") (pin "31") (pinfunction "P19_31") (pintype "unspecified+no_connect"))
    )
    (net (code "73") (name "unconnected-(U2-P23-Pad37)") (class "Default")
      (node (ref "U2") (pin "37") (pinfunction "P23_37") (pintype "unspecified+no_connect"))
    )
    (net (code "74") (name "unconnected-(U2-RX-Pad34)") (class "Default")
      (node (ref "U2") (pin "34") (pinfunction "RX_34") (pintype "unspecified+no_connect"))
    )
    (net (code "75") (name "unconnected-(U2-SD0-Pad21)") (class "Default")
      (node (ref "U2") (pin "21") (pinfunction "SD0_21") (pintype "unspecified+no_connect"))
    )
    (net (code "76") (name "unconnected-(U2-SD1-Pad22)") (class "Default")
      (node (ref "U2") (pin "22") (pinfunction "SD1_22") (pintype "unspecified+no_connect"))
    )
    (net (code "77") (name "unconnected-(U2-SD2-Pad4)") (class "Default")
      (node (ref "U2") (pin "4") (pinfunction "SD2_4") (pintype "unspecified+no_connect"))
    )
    (net (code "78") (name "unconnected-(U2-SD3-Pad3)") (class "Default")
      (node (ref "U2") (pin "3") (pinfunction "SD3_3") (pintype "unspecified+no_connect"))
    )
    (net (code "79") (name "unconnected-(U2-SVN-Pad16)") (class "Default")
      (node (ref "U2") (pin "16") (pinfunction "SVN_16") (pintype "unspecified+no_connect"))
    )
    (net (code "80") (name "unconnected-(U2-SVP-Pad17)") (class "Default")
      (node (ref "U2") (pin "17") (pinfunction "SVP_17") (pintype "unspecified+no_connect"))
    )
    (net (code "81") (name "unconnected-(U2-TX-Pad35)") (class "Default")
      (node (ref "U2") (pin "35") (pinfunction "TX_35") (pintype "unspecified+no_connect"))
    )
    (net (code "82") (name "unconnected-(U2-Vin_(5V)-Pad1)") (class "Default")
      (node (ref "U2") (pin "1") (pinfunction "Vin_(5V)_1") (pintype "unspecified+no_connect"))
    )
    (net (code "83") (name "unconnected-(U6-IO0-Pad11)") (class "Default")
      (node (ref "U6") (pin "11") (pinfunction "IO0_11") (pintype "unspecified+no_connect"))
    )
    (net (code "84") (name "unconnected-(U6-IO1-Pad15)") (class "Default")
      (node (ref "U6") (pin "15") (pinfunction "IO1_15") (pintype "unspecified+no_connect"))
    )
    (net (code "85") (name "unconnected-(U6-IO3-Pad14)") (class "Default")
      (node (ref "U6") (pin "14") (pinfunction "IO3_14") (pintype "unspecified+no_connect"))
    )
    (net (code "86") (name "unconnected-(U6-IO16-Pad10)") (class "Default")
      (node (ref "U6") (pin "10") (pinfunction "IO16_10") (pintype "unspecified+no_connect"))
    )
  )
)
